# EJ1-PCB.net
KiCad netlist of a schematic drawn in Altium Designer
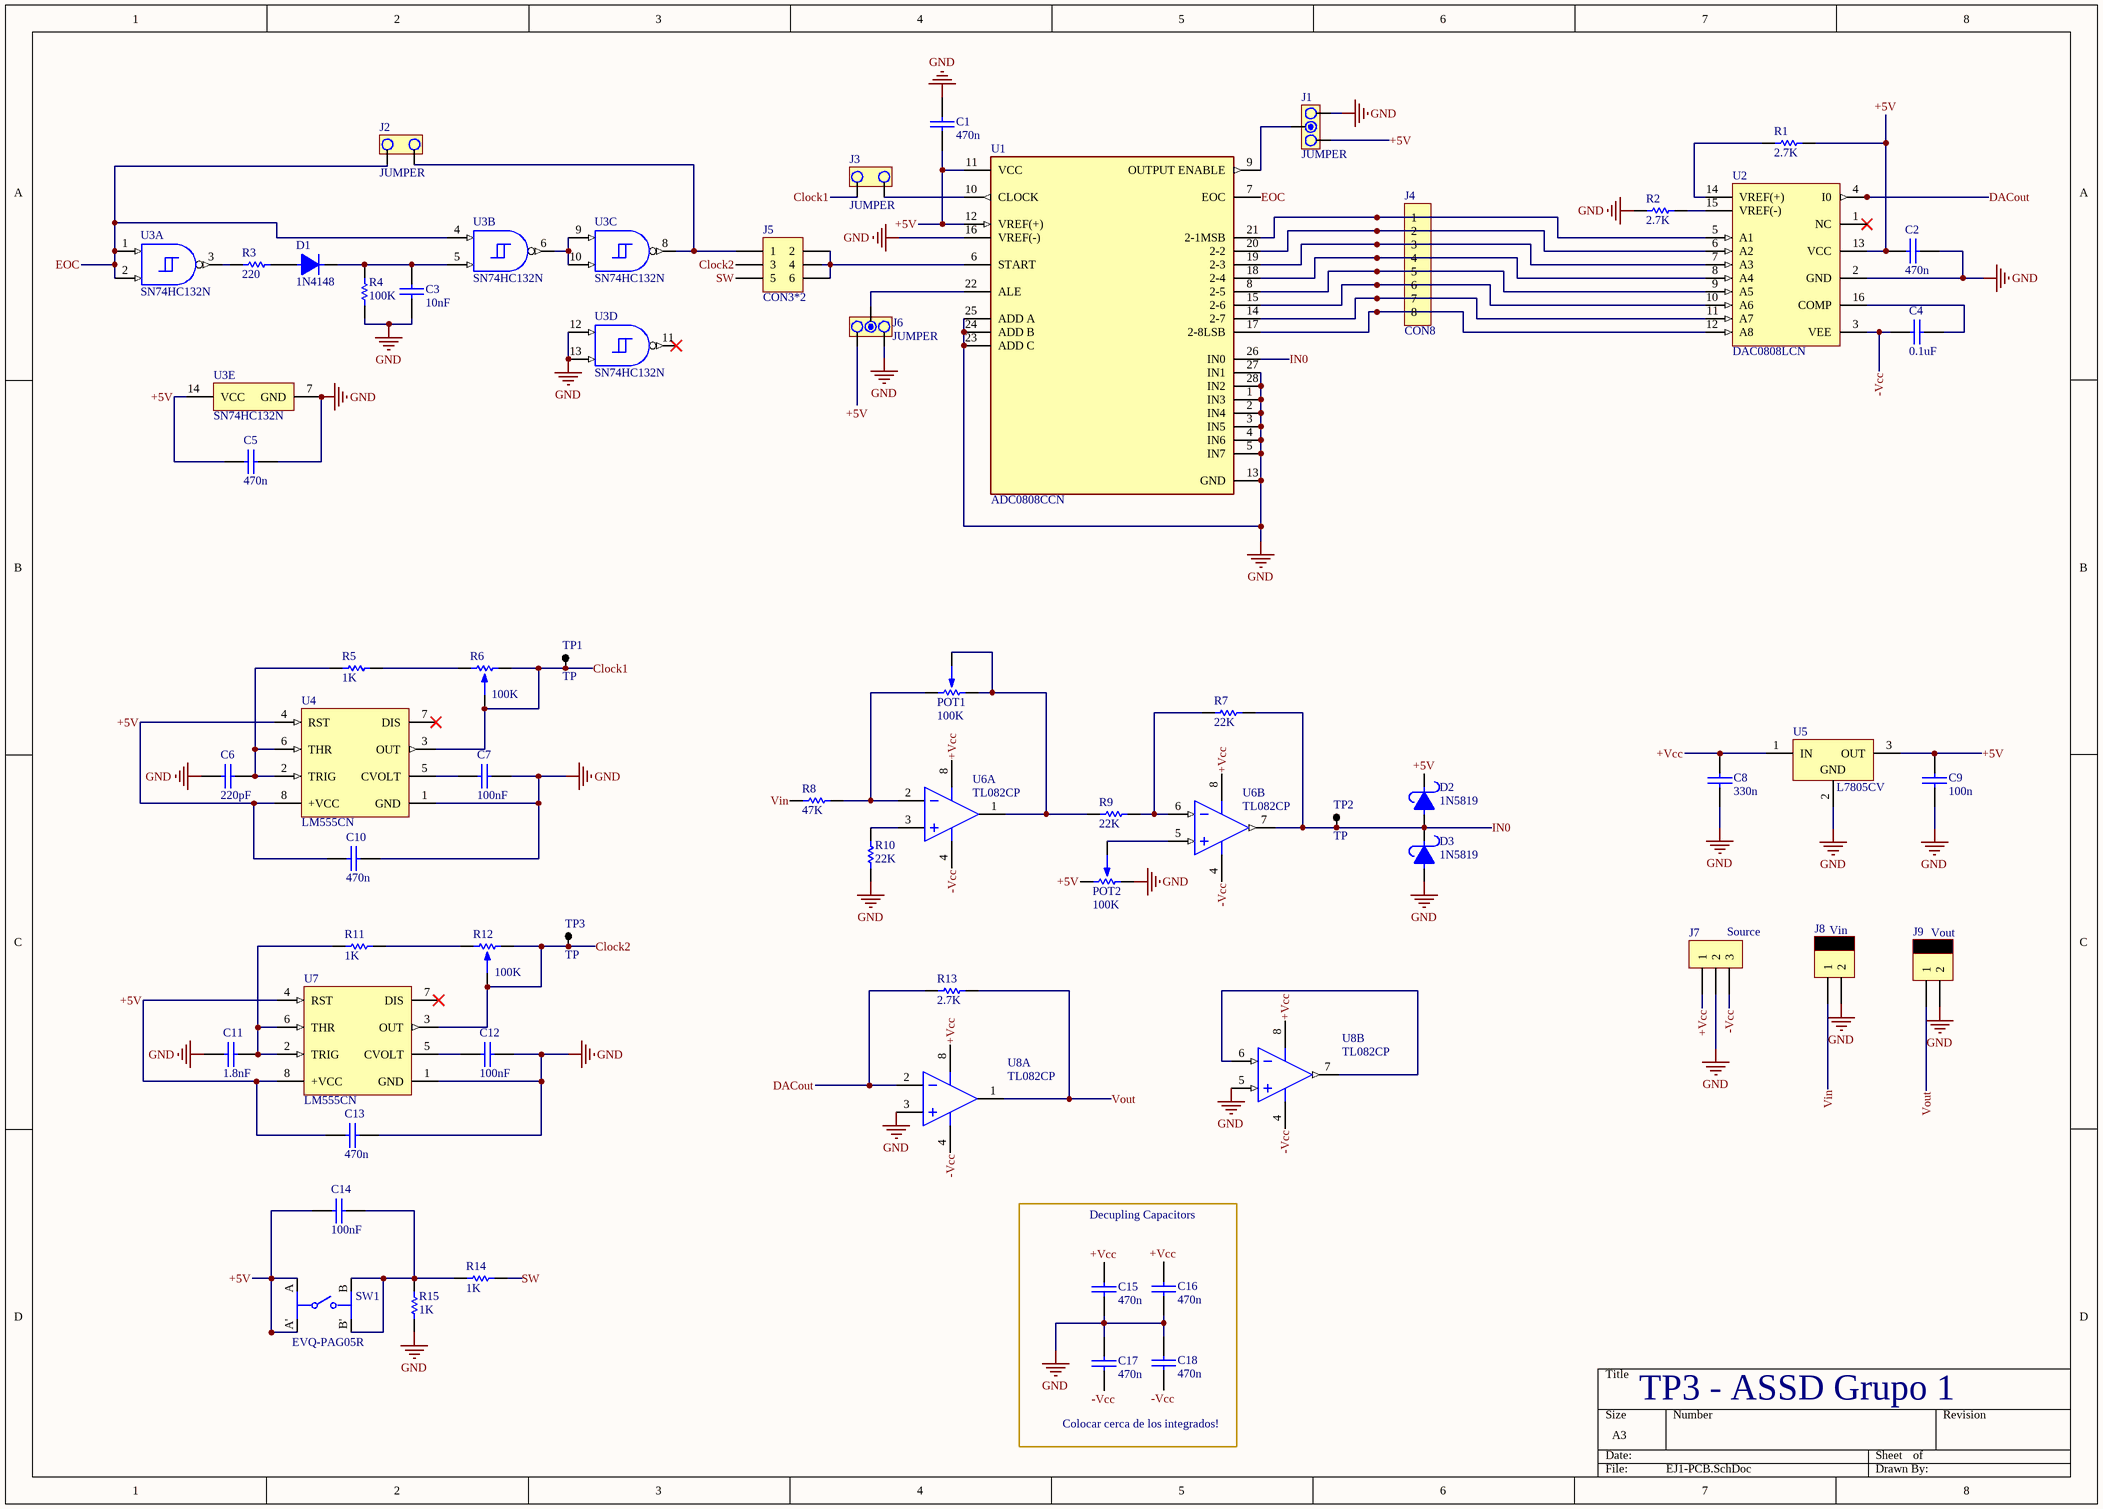
[diagram p0: EJ1-PCB.SchDoc]

(export (version "E")
  (design (tool "Eeschema 10.0.6"))
  (components
    (comp (ref "C1") (value "470n") (footprint "0805") (libsource (lib "LIBEBAL") (part "CAP")))
    (comp (ref "C2") (value "470n") (footprint "0805") (libsource (lib "LIBEBAL") (part "CAP")))
    (comp (ref "C3") (value "10nF") (footprint "0805") (libsource (lib "LIBEBAL") (part "CAP")))
    (comp (ref "C4") (value "0.1uF") (footprint "0805") (libsource (lib "LIBEBAL") (part "CAP")))
    (comp (ref "C5") (value "470n") (footprint "0805") (libsource (lib "LIBEBAL") (part "CAP")))
    (comp (ref "C6") (value "220pF") (footprint "0805") (libsource (lib "LIBEBAL") (part "CAP")))
    (comp (ref "C7") (value "100nF") (footprint "0805") (libsource (lib "LIBEBAL") (part "CAP")))
    (comp (ref "C8") (value "330n") (footprint "0805") (libsource (lib "LIBEBAL") (part "CAP")))
    (comp (ref "C9") (value "100n") (footprint "0805") (libsource (lib "LIBEBAL") (part "CAP")))
    (comp (ref "C10") (value "470n") (footprint "0805") (libsource (lib "LIBEBAL") (part "CAP")))
    (comp (ref "C11") (value "1.8nF") (footprint "0805") (libsource (lib "LIBEBAL") (part "CAP")))
    (comp (ref "C12") (value "100nF") (footprint "0805") (libsource (lib "LIBEBAL") (part "CAP")))
    (comp (ref "C13") (value "470n") (footprint "0805") (libsource (lib "LIBEBAL") (part "CAP")))
    (comp (ref "C14") (value "100nF") (footprint "0805") (libsource (lib "LIBEBAL") (part "CAP")))
    (comp (ref "C15") (value "470n") (footprint "0805") (libsource (lib "LIBEBAL") (part "CAP")))
    (comp (ref "C16") (value "470n") (footprint "0805") (libsource (lib "LIBEBAL") (part "CAP")))
    (comp (ref "C17") (value "470n") (footprint "0805") (libsource (lib "LIBEBAL") (part "CAP")))
    (comp (ref "C18") (value "470n") (footprint "0805") (libsource (lib "LIBEBAL") (part "CAP")))
    (comp (ref "D1") (value "1N4148") (footprint "DO41") (libsource (lib "LIBEBAL Tobi") (part "DIODO")))
    (comp (ref "D2") (value "1N5819") (footprint "DO41") (libsource (lib "LIBEBAL") (part "DIODO SCHOTTKY")))
    (comp (ref "D3") (value "1N5819") (footprint "DO41") (libsource (lib "LIBEBAL") (part "DIODO SCHOTTKY")))
    (comp (ref "J1") (value "JUMPER") (footprint "JUMPER3") (libsource (lib "") (part "JUMPER3_1")))
    (comp (ref "J2")
      (value "JUMPER")
      (footprint "JUMPER2")
      (description "Just in case HC132 does not work")
      (libsource (lib "LIBEBAL Tobi") (part "JUMPER"))
    )
    (comp (ref "J3") (value "JUMPER") (footprint "JUMPER2") (libsource (lib "LIBEBAL Tobi") (part "JUMPER")))
    (comp (ref "J4") (value "CON8") (footprint "SIP8") (libsource (lib "LIBEBAL") (part "CON8")))
    (comp (ref "J5") (value "CON3*2") (footprint "SIP3*2") (libsource (lib "LIBEBAL") (part "CON3*2")))
    (comp (ref "J6") (value "JUMPER") (footprint "JUMPER3") (libsource (lib "LIBEBAL Tobi") (part "JUMPER3")))
    (comp (ref "J7") (value "Source") (footprint "BORNERA3") (libsource (lib "LIBEBAL") (part "BORNERA 3")))
    (comp (ref "J8") (value "Vin") (footprint "MOLEX2") (libsource (lib "LIBEBAL Tobi") (part "MOLEX2")))
    (comp (ref "J9") (value "Vout") (footprint "MOLEX2") (libsource (lib "LIBEBAL Tobi") (part "MOLEX2")))
    (comp (ref "POT1") (value "100K") (footprint "PRESET V") (libsource (lib "LIBEBAL") (part "PRESET")))
    (comp (ref "POT2") (value "100K") (footprint "PRESET V") (libsource (lib "LIBEBAL") (part "PRESET")))
    (comp (ref "R1") (value "2.7K") (footprint "0805") (libsource (lib "LIBEBAL") (part "RES")))
    (comp (ref "R2") (value "2.7K") (footprint "0805") (libsource (lib "LIBEBAL") (part "RES")))
    (comp (ref "R3") (value "220") (footprint "0805") (libsource (lib "LIBEBAL") (part "RES")))
    (comp (ref "R4") (value "100K") (footprint "0805") (libsource (lib "LIBEBAL") (part "RES")))
    (comp (ref "R5") (value "1K") (footprint "0805") (libsource (lib "LIBEBAL") (part "RES")))
    (comp (ref "R6") (value "100K") (footprint "PRESET V") (libsource (lib "LIBEBAL") (part "PRESET")))
    (comp (ref "R7") (value "22K") (footprint "0805") (libsource (lib "LIBEBAL") (part "RES")))
    (comp (ref "R8") (value "47K") (footprint "0805") (libsource (lib "LIBEBAL") (part "RES")))
    (comp (ref "R9") (value "22K") (footprint "0805") (libsource (lib "LIBEBAL") (part "RES")))
    (comp (ref "R10") (value "22K") (footprint "0805") (libsource (lib "LIBEBAL") (part "RES")))
    (comp (ref "R11") (value "1K") (footprint "0805") (libsource (lib "LIBEBAL") (part "RES")))
    (comp (ref "R12") (value "100K") (footprint "PRESET V") (libsource (lib "LIBEBAL") (part "PRESET")))
    (comp (ref "R13") (value "2.7K") (footprint "0805") (libsource (lib "LIBEBAL") (part "RES")))
    (comp (ref "R14") (value "1K") (footprint "0805") (libsource (lib "LIBEBAL") (part "RES")))
    (comp (ref "R15") (value "1K") (footprint "0805") (libsource (lib "LIBEBAL") (part "RES")))
    (comp (ref "SW1")
      (value "EVQ-PAG05R")
      (footprint "FP-EVQ-PAG05R-MFG")
      (description "SWITCH TACTILE SPST-NO 0.02A 15V")
      (libsource (lib "Altium Content Vault") (part "841f23923f71b23f3ea0ab5dfb78dcc"))
    )
    (comp (ref "TP1") (value "TP") (footprint "TPTH") (libsource (lib "LIBEBAL") (part "TP")))
    (comp (ref "TP2") (value "TP") (footprint "TPTH") (libsource (lib "LIBEBAL") (part "TP")))
    (comp (ref "TP3") (value "TP") (footprint "TPTH") (libsource (lib "LIBEBAL") (part "TP")))
    (comp (ref "U1")
      (value "ADC0808CCN")
      (footprint "FP-N0028A-MFG")
      (description "IC ADC 8BIT MPU 8CH MUX 28-DIP")
      (libsource (lib "Altium Content Vault") (part "9fa2e44bffd5cb458ee99d9d496f163"))
    )
    (comp (ref "U2")
      (value "DAC0808LCN")
      (footprint "NFG0016A")
      (description "8-Bit D/A Converter, 16-pin MDIP")
      (fields (field (name "MANUFACTURER") "Texas Instruments"))
      (libsource (lib "Altium Content Vault") (part "CON-DAC-DAC0808-16"))
    )
    (comp (ref "U3")
      (value "SN74HC132N")
      (footprint "N0014A")
      (description "Quadruple Positive-NAND Gates With Schmitt-Trigger Inputs, N0014A, TUBE")
      (fields
        (field (name "GENERIC PART NUMBER") "SN74HC132")
        (field (name "MANUFACTURER") "Texas Instruments")
      )
      (libsource (lib "Altium Content Vault") (part "TI-NAND-4-2IN-14_G-SCHMITT"))
    )
    (comp (ref "U4")
      (value "LM555CN")
      (footprint "N08E")
      (description "Timer, 8-pin MDIP")
      (fields (field (name "MANUFACTURER") "National Semiconductor"))
      (libsource (lib "Altium Content Vault") (part "AN-TIMER-LM555-8"))
    )
    (comp (ref "U5")
      (value "L7805CV")
      (footprint "TO220")
      (description "Positive Voltage Regulator, 5V, 3-Pin TO-220")
      (libsource (lib "Altium Content Vault") (part "PM-REG-L4940-SIL3"))
    )
    (comp (ref "U6")
      (value "TL082CP")
      (footprint "P0008A")
      (description "JFET-Input Operational Amplifier, 7 to 36 V, 0 to 70 degC, 8-pin DIP (P8), Pb-Free (RoHS)")
      (fields (field (name "MANUFACTURER") "Texas Instruments"))
      (libsource (lib "Altium Content Vault") (part "TI-AMP-D6-2-8_D"))
    )
    (comp (ref "U7")
      (value "LM555CN")
      (footprint "N08E")
      (description "Timer, 8-pin MDIP")
      (fields (field (name "MANUFACTURER") "National Semiconductor"))
      (libsource (lib "Altium Content Vault") (part "AN-TIMER-LM555-8"))
    )
    (comp (ref "U8")
      (value "TL082CP")
      (footprint "P0008A")
      (description "JFET-Input Operational Amplifier, 7 to 36 V, 0 to 70 degC, 8-pin DIP (P8), Pb-Free (RoHS)")
      (fields (field (name "MANUFACTURER") "Texas Instruments"))
      (libsource (lib "Altium Content Vault") (part "TI-AMP-D6-2-8_D"))
    )
  )
  (nets
    (net (code "1") (name "/+5V") (class "Default")
      (node (ref "C1") (pin "2") (pinfunction "2_2") (pintype "passive"))
      (node (ref "C10") (pin "1") (pinfunction "1_1") (pintype "passive"))
      (node (ref "C13") (pin "1") (pinfunction "1_1") (pintype "passive"))
      (node (ref "C14") (pin "2") (pinfunction "2_2") (pintype "passive"))
      (node (ref "C2") (pin "1") (pinfunction "1_1") (pintype "passive"))
      (node (ref "C5") (pin "1") (pinfunction "1_1") (pintype "passive"))
      (node (ref "C9") (pin "1") (pinfunction "1_1") (pintype "passive"))
      (node (ref "D2") (pin "2") (pinfunction "2_2") (pintype "passive"))
      (node (ref "J1") (pin "3") (pinfunction "3_3") (pintype "passive"))
      (node (ref "J6") (pin "3") (pinfunction "3_3") (pintype "passive"))
      (node (ref "POT2") (pin "1") (pinfunction "1_1") (pintype "passive"))
      (node (ref "R1") (pin "2") (pinfunction "2_2") (pintype "passive"))
      (node (ref "SW1") (pin "A") (pinfunction "A_A") (pintype "passive"))
      (node (ref "SW1") (pin "A'") (pinfunction "A'_A'") (pintype "passive"))
      (node (ref "U1") (pin "11") (pinfunction "VCC_11") (pintype "power_in"))
      (node (ref "U1") (pin "12") (pinfunction "VREF(+)_12") (pintype "input"))
      (node (ref "U2") (pin "13") (pinfunction "VCC_13") (pintype "power_in"))
      (node (ref "U3") (pin "14") (pinfunction "VCC_14") (pintype "power_in"))
      (node (ref "U4") (pin "4") (pinfunction "RST_4") (pintype "input"))
      (node (ref "U4") (pin "8") (pinfunction "+VCC_8") (pintype "power_in"))
      (node (ref "U5") (pin "3") (pinfunction "OUT_3") (pintype "power_in"))
      (node (ref "U7") (pin "4") (pinfunction "RST_4") (pintype "input"))
      (node (ref "U7") (pin "8") (pinfunction "+VCC_8") (pintype "power_in"))
    )
    (net (code "2") (name "/+Vcc") (class "Default")
      (node (ref "C15") (pin "1") (pinfunction "1_1") (pintype "passive"))
      (node (ref "C16") (pin "1") (pinfunction "1_1") (pintype "passive"))
      (node (ref "C8") (pin "1") (pinfunction "1_1") (pintype "passive"))
      (node (ref "J7") (pin "1") (pinfunction "1_1") (pintype "passive"))
      (node (ref "U5") (pin "1") (pinfunction "IN_1") (pintype "power_in"))
      (node (ref "U6") (pin "8") (pinfunction "VCC+_8") (pintype "passive"))
      (node (ref "U8") (pin "8") (pinfunction "VCC+_8") (pintype "passive"))
    )
    (net (code "3") (name "/-Vcc") (class "Default")
      (node (ref "C17") (pin "2") (pinfunction "2_2") (pintype "passive"))
      (node (ref "C18") (pin "2") (pinfunction "2_2") (pintype "passive"))
      (node (ref "C4") (pin "1") (pinfunction "1_1") (pintype "passive"))
      (node (ref "J7") (pin "3") (pinfunction "3_3") (pintype "passive"))
      (node (ref "U2") (pin "3") (pinfunction "VEE_3") (pintype "power_in"))
      (node (ref "U6") (pin "4") (pinfunction "VCC-_4") (pintype "passive"))
      (node (ref "U8") (pin "4") (pinfunction "VCC-_4") (pintype "passive"))
    )
    (net (code "4") (name "/Clock1") (class "Default")
      (node (ref "J3") (pin "2") (pinfunction "2_2") (pintype "passive"))
      (node (ref "R6") (pin "1") (pinfunction "1_1") (pintype "passive"))
      (node (ref "R6") (pin "2") (pinfunction "2_2") (pintype "passive"))
      (node (ref "TP1") (pin "1") (pinfunction "1_1") (pintype "passive"))
      (node (ref "U4") (pin "3") (pinfunction "OUT_3") (pintype "output"))
    )
    (net (code "5") (name "/Clock2") (class "Default")
      (node (ref "J5") (pin "3") (pinfunction "3_3") (pintype "passive"))
      (node (ref "R12") (pin "1") (pinfunction "1_1") (pintype "passive"))
      (node (ref "R12") (pin "2") (pinfunction "2_2") (pintype "passive"))
      (node (ref "TP3") (pin "1") (pinfunction "1_1") (pintype "passive"))
      (node (ref "U7") (pin "3") (pinfunction "OUT_3") (pintype "output"))
    )
    (net (code "6") (name "/DACout") (class "Default")
      (node (ref "R13") (pin "1") (pinfunction "1_1") (pintype "passive"))
      (node (ref "U2") (pin "4") (pinfunction "I0_4") (pintype "output"))
      (node (ref "U8") (pin "2") (pinfunction "IN1-_2") (pintype "passive"))
    )
    (net (code "7") (name "/EOC") (class "Default")
      (node (ref "J2") (pin "2") (pinfunction "2_2") (pintype "passive"))
      (node (ref "U1") (pin "7") (pinfunction "EOC_7") (pintype "passive"))
      (node (ref "U3") (pin "1") (pinfunction "1A_1") (pintype "input"))
      (node (ref "U3") (pin "2") (pinfunction "1B_2") (pintype "input"))
      (node (ref "U3") (pin "4") (pinfunction "2A_4") (pintype "input"))
    )
    (net (code "8") (name "/IN0") (class "Default")
      (node (ref "D2") (pin "1") (pinfunction "1_1") (pintype "passive"))
      (node (ref "D3") (pin "2") (pinfunction "2_2") (pintype "passive"))
      (node (ref "R7") (pin "2") (pinfunction "2_2") (pintype "passive"))
      (node (ref "TP2") (pin "1") (pinfunction "1_1") (pintype "passive"))
      (node (ref "U1") (pin "26") (pinfunction "IN0_26") (pintype "passive"))
      (node (ref "U6") (pin "7") (pinfunction "OUT2_7") (pintype "passive"))
    )
    (net (code "9") (name "/SW") (class "Default")
      (node (ref "J5") (pin "5") (pinfunction "5_5") (pintype "passive"))
      (node (ref "R14") (pin "1") (pinfunction "1_1") (pintype "passive"))
    )
    (net (code "10") (name "/Vin") (class "Default")
      (node (ref "J8") (pin "1") (pinfunction "1_1") (pintype "passive"))
      (node (ref "R8") (pin "1") (pinfunction "1_1") (pintype "passive"))
    )
    (net (code "11") (name "/Vout") (class "Default")
      (node (ref "J9") (pin "1") (pinfunction "1_1") (pintype "passive"))
      (node (ref "R13") (pin "2") (pinfunction "2_2") (pintype "passive"))
      (node (ref "U8") (pin "1") (pinfunction "OUT1_1") (pintype "passive"))
    )
    (net (code "12") (name "GND") (class "Default")
      (node (ref "C1") (pin "1") (pinfunction "1_1") (pintype "passive"))
      (node (ref "C10") (pin "2") (pinfunction "2_2") (pintype "passive"))
      (node (ref "C11") (pin "2") (pinfunction "2_2") (pintype "passive"))
      (node (ref "C12") (pin "2") (pinfunction "2_2") (pintype "passive"))
      (node (ref "C13") (pin "2") (pinfunction "2_2") (pintype "passive"))
      (node (ref "C15") (pin "2") (pinfunction "2_2") (pintype "passive"))
      (node (ref "C16") (pin "2") (pinfunction "2_2") (pintype "passive"))
      (node (ref "C17") (pin "1") (pinfunction "1_1") (pintype "passive"))
      (node (ref "C18") (pin "1") (pinfunction "1_1") (pintype "passive"))
      (node (ref "C2") (pin "2") (pinfunction "2_2") (pintype "passive"))
      (node (ref "C3") (pin "2") (pinfunction "2_2") (pintype "passive"))
      (node (ref "C5") (pin "2") (pinfunction "2_2") (pintype "passive"))
      (node (ref "C6") (pin "2") (pinfunction "2_2") (pintype "passive"))
      (node (ref "C7") (pin "2") (pinfunction "2_2") (pintype "passive"))
      (node (ref "C8") (pin "2") (pinfunction "2_2") (pintype "passive"))
      (node (ref "C9") (pin "2") (pinfunction "2_2") (pintype "passive"))
      (node (ref "D3") (pin "1") (pinfunction "1_1") (pintype "passive"))
      (node (ref "J1") (pin "1") (pinfunction "1_1") (pintype "passive"))
      (node (ref "J6") (pin "1") (pinfunction "1_1") (pintype "passive"))
      (node (ref "J7") (pin "2") (pinfunction "2_2") (pintype "passive"))
      (node (ref "J8") (pin "2") (pinfunction "2_2") (pintype "passive"))
      (node (ref "J9") (pin "2") (pinfunction "2_2") (pintype "passive"))
      (node (ref "POT2") (pin "3") (pinfunction "3_3") (pintype "passive"))
      (node (ref "R10") (pin "2") (pinfunction "2_2") (pintype "passive"))
      (node (ref "R15") (pin "1") (pinfunction "1_1") (pintype "passive"))
      (node (ref "R2") (pin "1") (pinfunction "1_1") (pintype "passive"))
      (node (ref "R4") (pin "1") (pinfunction "1_1") (pintype "passive"))
      (node (ref "U1") (pin "1") (pinfunction "IN3_1") (pintype "passive"))
      (node (ref "U1") (pin "13") (pinfunction "GND_13") (pintype "power_in"))
      (node (ref "U1") (pin "16") (pinfunction "VREF(-)_16") (pintype "passive"))
      (node (ref "U1") (pin "2") (pinfunction "IN4_2") (pintype "passive"))
      (node (ref "U1") (pin "23") (pinfunction "ADD_C_23") (pintype "passive"))
      (node (ref "U1") (pin "24") (pinfunction "ADD_B_24") (pintype "passive"))
      (node (ref "U1") (pin "25") (pinfunction "ADD_A_25") (pintype "passive"))
      (node (ref "U1") (pin "27") (pinfunction "IN1_27") (pintype "passive"))
      (node (ref "U1") (pin "28") (pinfunction "IN2_28") (pintype "passive"))
      (node (ref "U1") (pin "3") (pinfunction "IN5_3") (pintype "passive"))
      (node (ref "U1") (pin "4") (pinfunction "IN6_4") (pintype "passive"))
      (node (ref "U1") (pin "5") (pinfunction "IN7_5") (pintype "passive"))
      (node (ref "U2") (pin "2") (pinfunction "GND_2") (pintype "power_in"))
      (node (ref "U3") (pin "12") (pinfunction "4A_12") (pintype "input"))
      (node (ref "U3") (pin "13") (pinfunction "4B_13") (pintype "input"))
      (node (ref "U3") (pin "7") (pinfunction "GND_7") (pintype "power_in"))
      (node (ref "U4") (pin "1") (pinfunction "GND_1") (pintype "power_in"))
      (node (ref "U5") (pin "2") (pinfunction "GND_2") (pintype "power_in"))
      (node (ref "U7") (pin "1") (pinfunction "GND_1") (pintype "power_in"))
      (node (ref "U8") (pin "3") (pinfunction "IN1+_3") (pintype "passive"))
      (node (ref "U8") (pin "5") (pinfunction "IN2+_5") (pintype "passive"))
    )
    (net (code "13") (name "Net-(C14-Pad1)") (class "Default")
      (node (ref "C14") (pin "1") (pinfunction "1_1") (pintype "passive"))
      (node (ref "R14") (pin "2") (pinfunction "2_2") (pintype "passive"))
      (node (ref "R15") (pin "2") (pinfunction "2_2") (pintype "passive"))
      (node (ref "SW1") (pin "B") (pinfunction "B_B") (pintype "passive"))
      (node (ref "SW1") (pin "B'") (pinfunction "B'_B'") (pintype "passive"))
    )
    (net (code "14") (name "Net-(D1-Pad1)") (class "Default")
      (node (ref "D1") (pin "1") (pinfunction "1_1") (pintype "passive"))
      (node (ref "R3") (pin "2") (pinfunction "2_2") (pintype "passive"))
    )
    (net (code "15") (name "Net-(R5-Pad2)") (class "Default")
      (node (ref "R5") (pin "2") (pinfunction "2_2") (pintype "passive"))
      (node (ref "R6") (pin "3") (pinfunction "3_3") (pintype "passive"))
    )
    (net (code "16") (name "Net-(R11-Pad2)") (class "Default")
      (node (ref "R11") (pin "2") (pinfunction "2_2") (pintype "passive"))
      (node (ref "R12") (pin "3") (pinfunction "3_3") (pintype "passive"))
    )
    (net (code "17") (name "Net-(U1-2-1MSB)") (class "Default")
      (node (ref "J4") (pin "1") (pinfunction "1_1") (pintype "tri_state"))
      (node (ref "U1") (pin "21") (pinfunction "2-1MSB_21") (pintype "passive"))
      (node (ref "U2") (pin "5") (pinfunction "A1_5") (pintype "input"))
    )
    (net (code "18") (name "Net-(U1-2-2)") (class "Default")
      (node (ref "J4") (pin "2") (pinfunction "2_2") (pintype "tri_state"))
      (node (ref "U1") (pin "20") (pinfunction "2-2_20") (pintype "passive"))
      (node (ref "U2") (pin "6") (pinfunction "A2_6") (pintype "input"))
    )
    (net (code "19") (name "Net-(U1-2-3)") (class "Default")
      (node (ref "J4") (pin "3") (pinfunction "3_3") (pintype "tri_state"))
      (node (ref "U1") (pin "19") (pinfunction "2-3_19") (pintype "passive"))
      (node (ref "U2") (pin "7") (pinfunction "A3_7") (pintype "input"))
    )
    (net (code "20") (name "Net-(U1-2-4)") (class "Default")
      (node (ref "J4") (pin "4") (pinfunction "4_4") (pintype "tri_state"))
      (node (ref "U1") (pin "18") (pinfunction "2-4_18") (pintype "passive"))
      (node (ref "U2") (pin "8") (pinfunction "A4_8") (pintype "input"))
    )
    (net (code "21") (name "Net-(U1-2-5)") (class "Default")
      (node (ref "J4") (pin "5") (pinfunction "5_5") (pintype "tri_state"))
      (node (ref "U1") (pin "8") (pinfunction "2-5_8") (pintype "passive"))
      (node (ref "U2") (pin "9") (pinfunction "A5_9") (pintype "input"))
    )
    (net (code "22") (name "Net-(U1-2-6)") (class "Default")
      (node (ref "J4") (pin "6") (pinfunction "6_6") (pintype "tri_state"))
      (node (ref "U1") (pin "15") (pinfunction "2-6_15") (pintype "passive"))
      (node (ref "U2") (pin "10") (pinfunction "A6_10") (pintype "input"))
    )
    (net (code "23") (name "Net-(U1-2-7)") (class "Default")
      (node (ref "J4") (pin "7") (pinfunction "7_7") (pintype "tri_state"))
      (node (ref "U1") (pin "14") (pinfunction "2-7_14") (pintype "passive"))
      (node (ref "U2") (pin "11") (pinfunction "A7_11") (pintype "input"))
    )
    (net (code "24") (name "Net-(U1-2-8LSB)") (class "Default")
      (node (ref "J4") (pin "8") (pinfunction "8_8") (pintype "tri_state"))
      (node (ref "U1") (pin "17") (pinfunction "2-8LSB_17") (pintype "passive"))
      (node (ref "U2") (pin "12") (pinfunction "A8_12") (pintype "input"))
    )
    (net (code "25") (name "Net-(U1-ALE)") (class "Default")
      (node (ref "J6") (pin "2") (pinfunction "2_2") (pintype "passive"))
      (node (ref "U1") (pin "22") (pinfunction "ALE_22") (pintype "passive"))
    )
    (net (code "26") (name "Net-(U1-CLOCK)") (class "Default")
      (node (ref "J3") (pin "1") (pinfunction "1_1") (pintype "passive"))
      (node (ref "U1") (pin "10") (pinfunction "CLOCK_10") (pintype "output"))
    )
    (net (code "27") (name "Net-(U1-OUTPUT_ENABLE)") (class "Default")
      (node (ref "J1") (pin "2") (pinfunction "2_2") (pintype "passive"))
      (node (ref "U1") (pin "9") (pinfunction "OUTPUT_ENABLE_9") (pintype "output"))
    )
    (net (code "28") (name "Net-(U1-START)") (class "Default")
      (node (ref "J5") (pin "2") (pinfunction "2_2") (pintype "passive"))
      (node (ref "J5") (pin "4") (pinfunction "4_4") (pintype "passive"))
      (node (ref "J5") (pin "6") (pinfunction "6_6") (pintype "passive"))
      (node (ref "U1") (pin "6") (pinfunction "START_6") (pintype "passive"))
    )
    (net (code "29") (name "Net-(U2-COMP)") (class "Default")
      (node (ref "C4") (pin "2") (pinfunction "2_2") (pintype "passive"))
      (node (ref "U2") (pin "16") (pinfunction "COMP_16") (pintype "passive"))
    )
    (net (code "30") (name "Net-(U2-VREF(+))") (class "Default")
      (node (ref "R1") (pin "1") (pinfunction "1_1") (pintype "passive"))
      (node (ref "U2") (pin "14") (pinfunction "VREF(+)_14") (pintype "power_in"))
    )
    (net (code "31") (name "Net-(U2-VREF(-))") (class "Default")
      (node (ref "R2") (pin "2") (pinfunction "2_2") (pintype "passive"))
      (node (ref "U2") (pin "15") (pinfunction "VREF(-)_15") (pintype "power_in"))
    )
    (net (code "32") (name "Net-(U3A-1Y)") (class "Default")
      (node (ref "R3") (pin "1") (pinfunction "1_1") (pintype "passive"))
      (node (ref "U3") (pin "3") (pinfunction "1Y_3") (pintype "output"))
    )
    (net (code "33") (name "Net-(U3B-2B)") (class "Default")
      (node (ref "C3") (pin "1") (pinfunction "1_1") (pintype "passive"))
      (node (ref "D1") (pin "2") (pinfunction "2_2") (pintype "passive"))
      (node (ref "R4") (pin "2") (pinfunction "2_2") (pintype "passive"))
      (node (ref "U3") (pin "5") (pinfunction "2B_5") (pintype "input"))
    )
    (net (code "34") (name "Net-(U3B-2Y)") (class "Default")
      (node (ref "U3") (pin "10") (pinfunction "3B_10") (pintype "input"))
      (node (ref "U3") (pin "6") (pinfunction "2Y_6") (pintype "output"))
      (node (ref "U3") (pin "9") (pinfunction "3A_9") (pintype "input"))
    )
    (net (code "35") (name "Net-(U3C-3Y)") (class "Default")
      (node (ref "J2") (pin "1") (pinfunction "1_1") (pintype "passive"))
      (node (ref "J5") (pin "1") (pinfunction "1_1") (pintype "passive"))
      (node (ref "U3") (pin "8") (pinfunction "3Y_8") (pintype "output"))
    )
    (net (code "36") (name "Net-(U4-CVOLT)") (class "Default")
      (node (ref "C7") (pin "1") (pinfunction "1_1") (pintype "passive"))
      (node (ref "U4") (pin "5") (pinfunction "CVOLT_5") (pintype "passive"))
    )
    (net (code "37") (name "Net-(U4-THR)") (class "Default")
      (node (ref "C6") (pin "1") (pinfunction "1_1") (pintype "passive"))
      (node (ref "R5") (pin "1") (pinfunction "1_1") (pintype "passive"))
      (node (ref "U4") (pin "2") (pinfunction "TRIG_2") (pintype "input"))
      (node (ref "U4") (pin "6") (pinfunction "THR_6") (pintype "input"))
    )
    (net (code "38") (name "Net-(U6A-IN1+)") (class "Default")
      (node (ref "R10") (pin "1") (pinfunction "1_1") (pintype "passive"))
      (node (ref "U6") (pin "3") (pinfunction "IN1+_3") (pintype "passive"))
    )
    (net (code "39") (name "Net-(U6A-IN1-)") (class "Default")
      (node (ref "POT1") (pin "1") (pinfunction "1_1") (pintype "passive"))
      (node (ref "R8") (pin "2") (pinfunction "2_2") (pintype "passive"))
      (node (ref "U6") (pin "2") (pinfunction "IN1-_2") (pintype "passive"))
    )
    (net (code "40") (name "Net-(U6A-OUT1)") (class "Default")
      (node (ref "POT1") (pin "2") (pinfunction "2_2") (pintype "passive"))
      (node (ref "POT1") (pin "3") (pinfunction "3_3") (pintype "passive"))
      (node (ref "R9") (pin "1") (pinfunction "1_1") (pintype "passive"))
      (node (ref "U6") (pin "1") (pinfunction "OUT1_1") (pintype "passive"))
    )
    (net (code "41") (name "Net-(U6B-IN2+)") (class "Default")
      (node (ref "POT2") (pin "2") (pinfunction "2_2") (pintype "passive"))
      (node (ref "U6") (pin "5") (pinfunction "IN2+_5") (pintype "passive"))
    )
    (net (code "42") (name "Net-(U6B-IN2-)") (class "Default")
      (node (ref "R7") (pin "1") (pinfunction "1_1") (pintype "passive"))
      (node (ref "R9") (pin "2") (pinfunction "2_2") (pintype "passive"))
      (node (ref "U6") (pin "6") (pinfunction "IN2-_6") (pintype "passive"))
    )
    (net (code "43") (name "Net-(U7-CVOLT)") (class "Default")
      (node (ref "C12") (pin "1") (pinfunction "1_1") (pintype "passive"))
      (node (ref "U7") (pin "5") (pinfunction "CVOLT_5") (pintype "passive"))
    )
    (net (code "44") (name "Net-(U7-THR)") (class "Default")
      (node (ref "C11") (pin "1") (pinfunction "1_1") (pintype "passive"))
      (node (ref "R11") (pin "1") (pinfunction "1_1") (pintype "passive"))
      (node (ref "U7") (pin "2") (pinfunction "TRIG_2") (pintype "input"))
      (node (ref "U7") (pin "6") (pinfunction "THR_6") (pintype "input"))
    )
    (net (code "45") (name "Net-(U8B-IN2-)") (class "Default")
      (node (ref "U8") (pin "6") (pinfunction "IN2-_6") (pintype "passive"))
      (node (ref "U8") (pin "7") (pinfunction "OUT2_7") (pintype "passive"))
    )
    (net (code "46") (name "unconnected-(U2-NC-Pad1)") (class "Default")
      (node (ref "U2") (pin "1") (pinfunction "NC_1") (pintype "passive+no_connect"))
    )
    (net (code "47") (name "unconnected-(U3D-4Y-Pad11)") (class "Default")
      (node (ref "U3") (pin "11") (pinfunction "4Y_11") (pintype "output+no_connect"))
    )
    (net (code "48") (name "unconnected-(U4-DIS-Pad7)") (class "Default")
      (node (ref "U4") (pin "7") (pinfunction "DIS_7") (pintype "open_collector+no_connect"))
    )
    (net (code "49") (name "unconnected-(U7-DIS-Pad7)") (class "Default")
      (node (ref "U7") (pin "7") (pinfunction "DIS_7") (pintype "open_collector+no_connect"))
    )
  )
)
